# Input.net
KiCad netlist of a schematic drawn in Altium Designer
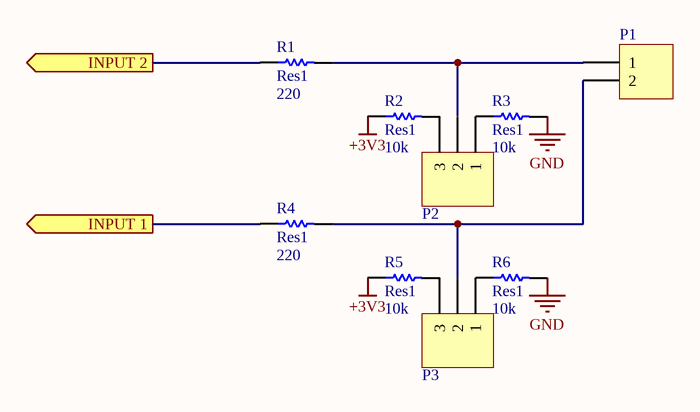
[diagram p0: Input.SchDoc]

(export (version "E")
  (design (tool "Eeschema 10.0.6"))
  (components
    (comp (ref "P1")
      (value "Header 2")
      (footprint "2 PIN TERM BLK")
      (description "Header, 2-Pin")
      (fields (field (name "PUBLISHER") "Altium Limited"))
      (libsource (lib "Miscellaneous Connectors") (part "Header 2"))
    )
    (comp (ref "P2")
      (value "Header 3")
      (footprint "HDR1X3")
      (description "Header, 3-Pin")
      (fields (field (name "PUBLISHER") "Altium Limited"))
      (libsource (lib "Miscellaneous Connectors") (part "Header 3"))
    )
    (comp (ref "P3")
      (value "Header 3")
      (footprint "HDR1X3")
      (description "Header, 3-Pin")
      (fields (field (name "PUBLISHER") "Altium Limited"))
      (libsource (lib "Miscellaneous Connectors") (part "Header 3"))
    )
    (comp (ref "R1")
      (value "Res1")
      (footprint "6-0805_N")
      (description "Resistor")
      (fields (field (name "ALTIUM_VALUE") "220") (field (name "PUBLISHER") "Altium Limited"))
      (libsource (lib "Miscellaneous Devices") (part "Res1"))
    )
    (comp (ref "R2")
      (value "Res1")
      (footprint "6-0805_N")
      (description "Resistor")
      (fields (field (name "ALTIUM_VALUE") "10k") (field (name "PUBLISHER") "Altium Limited"))
      (libsource (lib "Miscellaneous Devices") (part "Res1"))
    )
    (comp (ref "R3")
      (value "Res1")
      (footprint "6-0805_N")
      (description "Resistor")
      (fields (field (name "ALTIUM_VALUE") "10k") (field (name "PUBLISHER") "Altium Limited"))
      (libsource (lib "Miscellaneous Devices") (part "Res1"))
    )
    (comp (ref "R4")
      (value "Res1")
      (footprint "6-0805_N")
      (description "Resistor")
      (fields (field (name "ALTIUM_VALUE") "220") (field (name "PUBLISHER") "Altium Limited"))
      (libsource (lib "Miscellaneous Devices") (part "Res1"))
    )
    (comp (ref "R5")
      (value "Res1")
      (footprint "6-0805_N")
      (description "Resistor")
      (fields (field (name "ALTIUM_VALUE") "10k") (field (name "PUBLISHER") "Altium Limited"))
      (libsource (lib "Miscellaneous Devices") (part "Res1"))
    )
    (comp (ref "R6")
      (value "Res1")
      (footprint "6-0805_N")
      (description "Resistor")
      (fields (field (name "ALTIUM_VALUE") "10k") (field (name "PUBLISHER") "Altium Limited"))
      (libsource (lib "Miscellaneous Devices") (part "Res1"))
    )
  )
  (nets
    (net (code "1") (name "+3V3") (class "Default")
      (node (ref "R2") (pin "1") (pinfunction "1_1") (pintype "passive"))
      (node (ref "R5") (pin "1") (pinfunction "1_1") (pintype "passive"))
    )
    (net (code "2") (name "/INPUT 1") (class "Default")
      (node (ref "R4") (pin "1") (pinfunction "1_1") (pintype "passive"))
    )
    (net (code "3") (name "/INPUT 2") (class "Default")
      (node (ref "R1") (pin "1") (pinfunction "1_1") (pintype "passive"))
    )
    (net (code "4") (name "GND") (class "Default")
      (node (ref "R3") (pin "2") (pinfunction "2_2") (pintype "passive"))
      (node (ref "R6") (pin "2") (pinfunction "2_2") (pintype "passive"))
    )
    (net (code "5") (name "Net-(P1-Pad1)") (class "Default")
      (node (ref "P1") (pin "1") (pinfunction "1_1") (pintype "passive"))
      (node (ref "P2") (pin "2") (pinfunction "2_2") (pintype "passive"))
      (node (ref "R1") (pin "2") (pinfunction "2_2") (pintype "passive"))
    )
    (net (code "6") (name "Net-(P1-Pad2)") (class "Default")
      (node (ref "P1") (pin "2") (pinfunction "2_2") (pintype "passive"))
      (node (ref "P3") (pin "2") (pinfunction "2_2") (pintype "passive"))
      (node (ref "R4") (pin "2") (pinfunction "2_2") (pintype "passive"))
    )
    (net (code "7") (name "Net-(P2-Pad1)") (class "Default")
      (node (ref "P2") (pin "1") (pinfunction "1_1") (pintype "passive"))
      (node (ref "R3") (pin "1") (pinfunction "1_1") (pintype "passive"))
    )
    (net (code "8") (name "Net-(P2-Pad3)") (class "Default")
      (node (ref "P2") (pin "3") (pinfunction "3_3") (pintype "passive"))
      (node (ref "R2") (pin "2") (pinfunction "2_2") (pintype "passive"))
    )
    (net (code "9") (name "Net-(P3-Pad1)") (class "Default")
      (node (ref "P3") (pin "1") (pinfunction "1_1") (pintype "passive"))
      (node (ref "R6") (pin "1") (pinfunction "1_1") (pintype "passive"))
    )
    (net (code "10") (name "Net-(P3-Pad3)") (class "Default")
      (node (ref "P3") (pin "3") (pinfunction "3_3") (pintype "passive"))
      (node (ref "R5") (pin "2") (pinfunction "2_2") (pintype "passive"))
    )
  )
)
